# ledrampsesquema.net
KiCad netlist of a schematic drawn in EAGLE
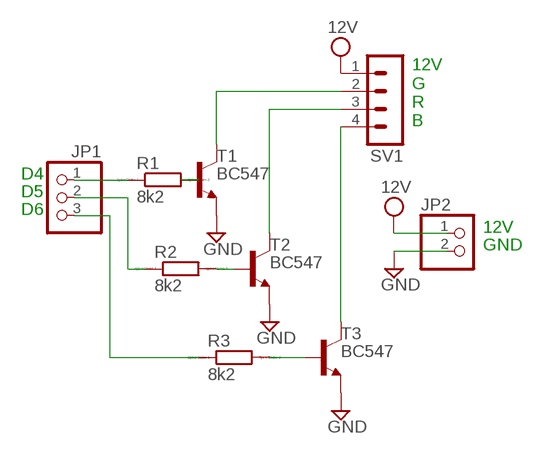
[diagram p0: schematic, sheet 1]

(export (version "E")
  (design (tool "Eeschema 10.0.6"))
  (components
    (comp (ref "JP1")
      (value "PINHD-1X3")
      (footprint "eagle-import:1X03")
      (libsource (lib "eagle-import") (part "PINHD-1X3"))
    )
    (comp (ref "JP2")
      (value "PINHD-1X2")
      (footprint "eagle-import:1X02")
      (libsource (lib "eagle-import") (part "PINHD-1X2"))
    )
    (comp (ref "R1")
      (value "8k2")
      (footprint "eagle-import:0204_7")
      (libsource (lib "eagle-import") (part "R0204/7"))
    )
    (comp (ref "R2")
      (value "8k2")
      (footprint "eagle-import:0204_7")
      (libsource (lib "eagle-import") (part "R0204/7"))
    )
    (comp (ref "R3")
      (value "8k2")
      (footprint "eagle-import:0204_7")
      (libsource (lib "eagle-import") (part "R0204/7"))
    )
    (comp (ref "SV1")
      (value "MA04-1")
      (footprint "eagle-import:MA04-1")
      (libsource (lib "eagle-import") (part "MA04-1"))
    )
    (comp (ref "T1")
      (value "BC547")
      (footprint "eagle-import:TO92")
      (libsource (lib "eagle-import") (part "BC547"))
    )
    (comp (ref "T2")
      (value "BC547")
      (footprint "eagle-import:TO92")
      (libsource (lib "eagle-import") (part "BC547"))
    )
    (comp (ref "T3")
      (value "BC547")
      (footprint "eagle-import:TO92")
      (libsource (lib "eagle-import") (part "BC547"))
    )
  )
  (nets
    (net (code "1") (name "12V") (class "Default")
      (node (ref "JP2") (pin "1") (pinfunction "1_1") (pintype "passive"))
      (node (ref "SV1") (pin "1") (pinfunction "1_1") (pintype "passive"))
    )
    (net (code "2") (name "GND") (class "Default")
      (node (ref "JP2") (pin "2") (pinfunction "2_2") (pintype "passive"))
      (node (ref "T1") (pin "1") (pinfunction "E_1") (pintype "passive"))
      (node (ref "T2") (pin "1") (pinfunction "E_1") (pintype "passive"))
      (node (ref "T3") (pin "1") (pinfunction "E_1") (pintype "passive"))
    )
    (net (code "3") (name "Net-(JP1-Pad1)") (class "Default")
      (node (ref "JP1") (pin "1") (pinfunction "1_1") (pintype "passive"))
      (node (ref "R1") (pin "1") (pinfunction "1_1") (pintype "passive"))
    )
    (net (code "4") (name "Net-(JP1-Pad2)") (class "Default")
      (node (ref "JP1") (pin "2") (pinfunction "2_2") (pintype "passive"))
      (node (ref "R2") (pin "1") (pinfunction "1_1") (pintype "passive"))
    )
    (net (code "5") (name "Net-(JP1-Pad3)") (class "Default")
      (node (ref "JP1") (pin "3") (pinfunction "3_3") (pintype "passive"))
      (node (ref "R3") (pin "1") (pinfunction "1_1") (pintype "passive"))
    )
    (net (code "6") (name "Net-(T1-B)") (class "Default")
      (node (ref "R1") (pin "2") (pinfunction "2_2") (pintype "passive"))
      (node (ref "T1") (pin "2") (pinfunction "B_2") (pintype "passive"))
    )
    (net (code "7") (name "Net-(T1-C)") (class "Default")
      (node (ref "SV1") (pin "2") (pinfunction "2_2") (pintype "passive"))
      (node (ref "T1") (pin "3") (pinfunction "C_3") (pintype "passive"))
    )
    (net (code "8") (name "Net-(T2-B)") (class "Default")
      (node (ref "R2") (pin "2") (pinfunction "2_2") (pintype "passive"))
      (node (ref "T2") (pin "2") (pinfunction "B_2") (pintype "passive"))
    )
    (net (code "9") (name "Net-(T2-C)") (class "Default")
      (node (ref "SV1") (pin "3") (pinfunction "3_3") (pintype "passive"))
      (node (ref "T2") (pin "3") (pinfunction "C_3") (pintype "passive"))
    )
    (net (code "10") (name "Net-(T3-B)") (class "Default")
      (node (ref "R3") (pin "2") (pinfunction "2_2") (pintype "passive"))
      (node (ref "T3") (pin "2") (pinfunction "B_2") (pintype "passive"))
    )
    (net (code "11") (name "Net-(T3-C)") (class "Default")
      (node (ref "SV1") (pin "4") (pinfunction "4_4") (pintype "passive"))
      (node (ref "T3") (pin "3") (pinfunction "C_3") (pintype "passive"))
    )
  )
)
